# Demrad_Atron_H24-H28.net
KiCad netlist of a schematic drawn in EAGLE
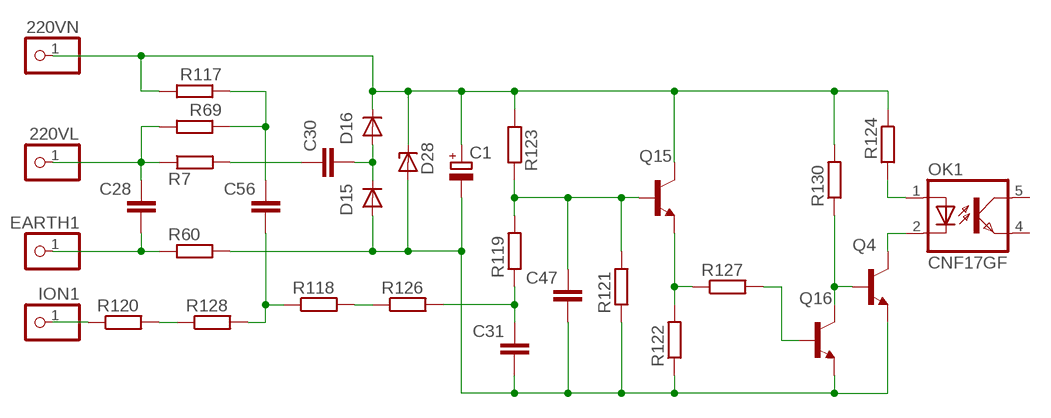
[diagram p0: schematic, sheet 1]

(export (version "E")
  (design (tool "Eeschema 10.0.6"))
  (components
    (comp (ref "220VL")
      (value "PINHD-1X1")
      (footprint "eagle-import:1X01")
      (libsource (lib "eagle-import") (part "PINHD-1X1"))
    )
    (comp (ref "220VN")
      (value "PINHD-1X1")
      (footprint "eagle-import:1X01")
      (libsource (lib "eagle-import") (part "PINHD-1X1"))
    )
    (comp (ref "C1")
      (value "CPOL-EU085CS-1R")
      (footprint "eagle-import:085CS_1R")
      (libsource (lib "eagle-import") (part "CPOL-EU085CS-1R"))
    )
    (comp (ref "C28")
      (value "C-EU050-024X044")
      (footprint "eagle-import:C050-024X044")
      (libsource (lib "eagle-import") (part "C-EU050-024X044"))
    )
    (comp (ref "C30")
      (value "C-EU050-024X044")
      (footprint "eagle-import:C050-024X044")
      (libsource (lib "eagle-import") (part "C-EU050-024X044"))
    )
    (comp (ref "C31")
      (value "C-EU050-024X044")
      (footprint "eagle-import:C050-024X044")
      (libsource (lib "eagle-import") (part "C-EU050-024X044"))
    )
    (comp (ref "C47")
      (value "C-EU050-024X044")
      (footprint "eagle-import:C050-024X044")
      (libsource (lib "eagle-import") (part "C-EU050-024X044"))
    )
    (comp (ref "C56")
      (value "C-EU050-024X044")
      (footprint "eagle-import:C050-024X044")
      (libsource (lib "eagle-import") (part "C-EU050-024X044"))
    )
    (comp (ref "D15")
      (value "1N4004")
      (footprint "eagle-import:DO41-10")
      (libsource (lib "eagle-import") (part "1N4004"))
    )
    (comp (ref "D16")
      (value "1N4004")
      (footprint "eagle-import:DO41-10")
      (libsource (lib "eagle-import") (part "1N4004"))
    )
    (comp (ref "D28")
      (value "ZENER-DIODEC1702-15")
      (footprint "eagle-import:C1702-15")
      (libsource (lib "eagle-import") (part "ZENER-DIODEC1702-15"))
    )
    (comp (ref "EARTH1")
      (value "PINHD-1X1")
      (footprint "eagle-import:1X01")
      (libsource (lib "eagle-import") (part "PINHD-1X1"))
    )
    (comp (ref "ION1")
      (value "PINHD-1X1")
      (footprint "eagle-import:1X01")
      (libsource (lib "eagle-import") (part "PINHD-1X1"))
    )
    (comp (ref "OK1")
      (value "CNF17GF")
      (footprint "eagle-import:DIL06B")
      (libsource (lib "eagle-import") (part "CNF17GF"))
    )
    (comp (ref "Q4")
      (value "BJT_NPN_TO-92_CBE")
      (footprint "eagle-import:TO92")
      (libsource (lib "eagle-import") (part "BJT_NPN_TO-92_CBE"))
    )
    (comp (ref "Q15")
      (value "BJT_NPN_TO-92_CBE")
      (footprint "eagle-import:TO92")
      (libsource (lib "eagle-import") (part "BJT_NPN_TO-92_CBE"))
    )
    (comp (ref "Q16")
      (value "BJT_NPN_TO-92_CBE")
      (footprint "eagle-import:TO92")
      (libsource (lib "eagle-import") (part "BJT_NPN_TO-92_CBE"))
    )
    (comp (ref "R7")
      (value "R-EU_M0805")
      (footprint "eagle-import:M0805")
      (libsource (lib "eagle-import") (part "R-EU_M0805"))
    )
    (comp (ref "R60")
      (value "R-EU_M0805")
      (footprint "eagle-import:M0805")
      (libsource (lib "eagle-import") (part "R-EU_M0805"))
    )
    (comp (ref "R69")
      (value "R-EU_M0805")
      (footprint "eagle-import:M0805")
      (libsource (lib "eagle-import") (part "R-EU_M0805"))
    )
    (comp (ref "R117")
      (value "R-EU_M0805")
      (footprint "eagle-import:M0805")
      (libsource (lib "eagle-import") (part "R-EU_M0805"))
    )
    (comp (ref "R118")
      (value "R-EU_M0805")
      (footprint "eagle-import:M0805")
      (libsource (lib "eagle-import") (part "R-EU_M0805"))
    )
    (comp (ref "R119")
      (value "R-EU_M0805")
      (footprint "eagle-import:M0805")
      (libsource (lib "eagle-import") (part "R-EU_M0805"))
    )
    (comp (ref "R120")
      (value "R-EU_M0805")
      (footprint "eagle-import:M0805")
      (libsource (lib "eagle-import") (part "R-EU_M0805"))
    )
    (comp (ref "R121")
      (value "R-EU_M0805")
      (footprint "eagle-import:M0805")
      (libsource (lib "eagle-import") (part "R-EU_M0805"))
    )
    (comp (ref "R122")
      (value "R-EU_M0805")
      (footprint "eagle-import:M0805")
      (libsource (lib "eagle-import") (part "R-EU_M0805"))
    )
    (comp (ref "R123")
      (value "R-EU_M0805")
      (footprint "eagle-import:M0805")
      (libsource (lib "eagle-import") (part "R-EU_M0805"))
    )
    (comp (ref "R124")
      (value "R-EU_M0805")
      (footprint "eagle-import:M0805")
      (libsource (lib "eagle-import") (part "R-EU_M0805"))
    )
    (comp (ref "R126")
      (value "R-EU_M0805")
      (footprint "eagle-import:M0805")
      (libsource (lib "eagle-import") (part "R-EU_M0805"))
    )
    (comp (ref "R127")
      (value "R-EU_M0805")
      (footprint "eagle-import:M0805")
      (libsource (lib "eagle-import") (part "R-EU_M0805"))
    )
    (comp (ref "R128")
      (value "R-EU_M0805")
      (footprint "eagle-import:M0805")
      (libsource (lib "eagle-import") (part "R-EU_M0805"))
    )
    (comp (ref "R130")
      (value "R-EU_M0805")
      (footprint "eagle-import:M0805")
      (libsource (lib "eagle-import") (part "R-EU_M0805"))
    )
  )
  (nets
    (net (code "1") (name "Net-(220VL-Pad1)") (class "Default")
      (node (ref "220VL") (pin "1") (pinfunction "1_1") (pintype "passive"))
      (node (ref "C28") (pin "1") (pinfunction "1_1") (pintype "passive"))
      (node (ref "R69") (pin "2") (pinfunction "2_2") (pintype "passive"))
      (node (ref "R7") (pin "1") (pinfunction "1_1") (pintype "passive"))
    )
    (net (code "2") (name "Net-(C28-Pad2)") (class "Default")
      (node (ref "C28") (pin "2") (pinfunction "2_2") (pintype "passive"))
      (node (ref "EARTH1") (pin "1") (pinfunction "1_1") (pintype "passive"))
      (node (ref "R60") (pin "1") (pinfunction "1_1") (pintype "passive"))
    )
    (net (code "3") (name "Net-(C30-Pad1)") (class "Default")
      (node (ref "C30") (pin "1") (pinfunction "1_1") (pintype "passive"))
      (node (ref "R7") (pin "2") (pinfunction "2_2") (pintype "passive"))
    )
    (net (code "4") (name "Net-(C30-Pad2)") (class "Default")
      (node (ref "C30") (pin "2") (pinfunction "2_2") (pintype "passive"))
      (node (ref "D15") (pin "C") (pinfunction "C_C") (pintype "passive"))
      (node (ref "D16") (pin "A") (pinfunction "A_A") (pintype "passive"))
    )
    (net (code "5") (name "Net-(C31-Pad1)") (class "Default")
      (node (ref "C31") (pin "1") (pinfunction "1_1") (pintype "passive"))
      (node (ref "R119") (pin "1") (pinfunction "1_1") (pintype "passive"))
      (node (ref "R126") (pin "2") (pinfunction "2_2") (pintype "passive"))
    )
    (net (code "6") (name "Net-(C56-Pad1)") (class "Default")
      (node (ref "C56") (pin "1") (pinfunction "1_1") (pintype "passive"))
      (node (ref "R117") (pin "1") (pinfunction "1_1") (pintype "passive"))
      (node (ref "R69") (pin "1") (pinfunction "1_1") (pintype "passive"))
    )
    (net (code "7") (name "Net-(C56-Pad2)") (class "Default")
      (node (ref "C56") (pin "2") (pinfunction "2_2") (pintype "passive"))
      (node (ref "R118") (pin "1") (pinfunction "1_1") (pintype "passive"))
      (node (ref "R128") (pin "2") (pinfunction "2_2") (pintype "passive"))
    )
    (net (code "8") (name "Net-(ION1-Pad1)") (class "Default")
      (node (ref "ION1") (pin "1") (pinfunction "1_1") (pintype "passive"))
      (node (ref "R120") (pin "1") (pinfunction "1_1") (pintype "passive"))
    )
    (net (code "9") (name "Net-(OK1-A)") (class "Default")
      (node (ref "OK1") (pin "1") (pinfunction "A_1") (pintype "passive"))
      (node (ref "R124") (pin "2") (pinfunction "2_2") (pintype "passive"))
    )
    (net (code "10") (name "Net-(OK1-C)") (class "Default")
      (node (ref "OK1") (pin "2") (pinfunction "C_2") (pintype "passive"))
      (node (ref "Q4") (pin "1") (pinfunction "C_1") (pintype "passive"))
    )
    (net (code "11") (name "Net-(Q15-B)") (class "Default")
      (node (ref "C47") (pin "1") (pinfunction "1_1") (pintype "passive"))
      (node (ref "Q15") (pin "2") (pinfunction "B_2") (pintype "passive"))
      (node (ref "R119") (pin "2") (pinfunction "2_2") (pintype "passive"))
      (node (ref "R121") (pin "2") (pinfunction "2_2") (pintype "passive"))
      (node (ref "R123") (pin "1") (pinfunction "1_1") (pintype "passive"))
    )
    (net (code "12") (name "Net-(Q15-C)") (class "Default")
      (node (ref "220VN") (pin "1") (pinfunction "1_1") (pintype "passive"))
      (node (ref "C1") (pin "+") (pinfunction "+_+") (pintype "passive"))
      (node (ref "D16") (pin "C") (pinfunction "C_C") (pintype "passive"))
      (node (ref "D28") (pin "C") (pinfunction "C_C") (pintype "passive"))
      (node (ref "Q15") (pin "1") (pinfunction "C_1") (pintype "passive"))
      (node (ref "R117") (pin "2") (pinfunction "2_2") (pintype "passive"))
      (node (ref "R123") (pin "2") (pinfunction "2_2") (pintype "passive"))
      (node (ref "R124") (pin "1") (pinfunction "1_1") (pintype "passive"))
      (node (ref "R130") (pin "2") (pinfunction "2_2") (pintype "passive"))
    )
    (net (code "13") (name "Net-(Q15-E)") (class "Default")
      (node (ref "Q15") (pin "3") (pinfunction "E_3") (pintype "passive"))
      (node (ref "R122") (pin "2") (pinfunction "2_2") (pintype "passive"))
      (node (ref "R127") (pin "1") (pinfunction "1_1") (pintype "passive"))
    )
    (net (code "14") (name "Net-(Q16-B)") (class "Default")
      (node (ref "Q16") (pin "2") (pinfunction "B_2") (pintype "passive"))
      (node (ref "R127") (pin "2") (pinfunction "2_2") (pintype "passive"))
    )
    (net (code "15") (name "Net-(Q16-C)") (class "Default")
      (node (ref "Q16") (pin "1") (pinfunction "C_1") (pintype "passive"))
      (node (ref "Q4") (pin "2") (pinfunction "B_2") (pintype "passive"))
      (node (ref "R130") (pin "1") (pinfunction "1_1") (pintype "passive"))
    )
    (net (code "16") (name "Net-(Q16-E)") (class "Default")
      (node (ref "C1") (pin "-") (pinfunction "-_-") (pintype "passive"))
      (node (ref "C31") (pin "2") (pinfunction "2_2") (pintype "passive"))
      (node (ref "C47") (pin "2") (pinfunction "2_2") (pintype "passive"))
      (node (ref "D15") (pin "A") (pinfunction "A_A") (pintype "passive"))
      (node (ref "D28") (pin "A") (pinfunction "A_A") (pintype "passive"))
      (node (ref "Q16") (pin "3") (pinfunction "E_3") (pintype "passive"))
      (node (ref "Q4") (pin "3") (pinfunction "E_3") (pintype "passive"))
      (node (ref "R121") (pin "1") (pinfunction "1_1") (pintype "passive"))
      (node (ref "R122") (pin "1") (pinfunction "1_1") (pintype "passive"))
      (node (ref "R60") (pin "2") (pinfunction "2_2") (pintype "passive"))
    )
    (net (code "17") (name "Net-(R118-Pad2)") (class "Default")
      (node (ref "R118") (pin "2") (pinfunction "2_2") (pintype "passive"))
      (node (ref "R126") (pin "1") (pinfunction "1_1") (pintype "passive"))
    )
    (net (code "18") (name "Net-(R120-Pad2)") (class "Default")
      (node (ref "R120") (pin "2") (pinfunction "2_2") (pintype "passive"))
      (node (ref "R128") (pin "1") (pinfunction "1_1") (pintype "passive"))
    )
    (net (code "19") (name "unconnected-(OK1-COL-Pad5)") (class "Default")
      (node (ref "OK1") (pin "5") (pinfunction "COL_5") (pintype "passive"))
    )
    (net (code "20") (name "unconnected-(OK1-EMIT-Pad4)") (class "Default")
      (node (ref "OK1") (pin "4") (pinfunction "EMIT_4") (pintype "passive"))
    )
  )
)
